# servo_shield_v1.net
KiCad netlist of a schematic drawn in EAGLE
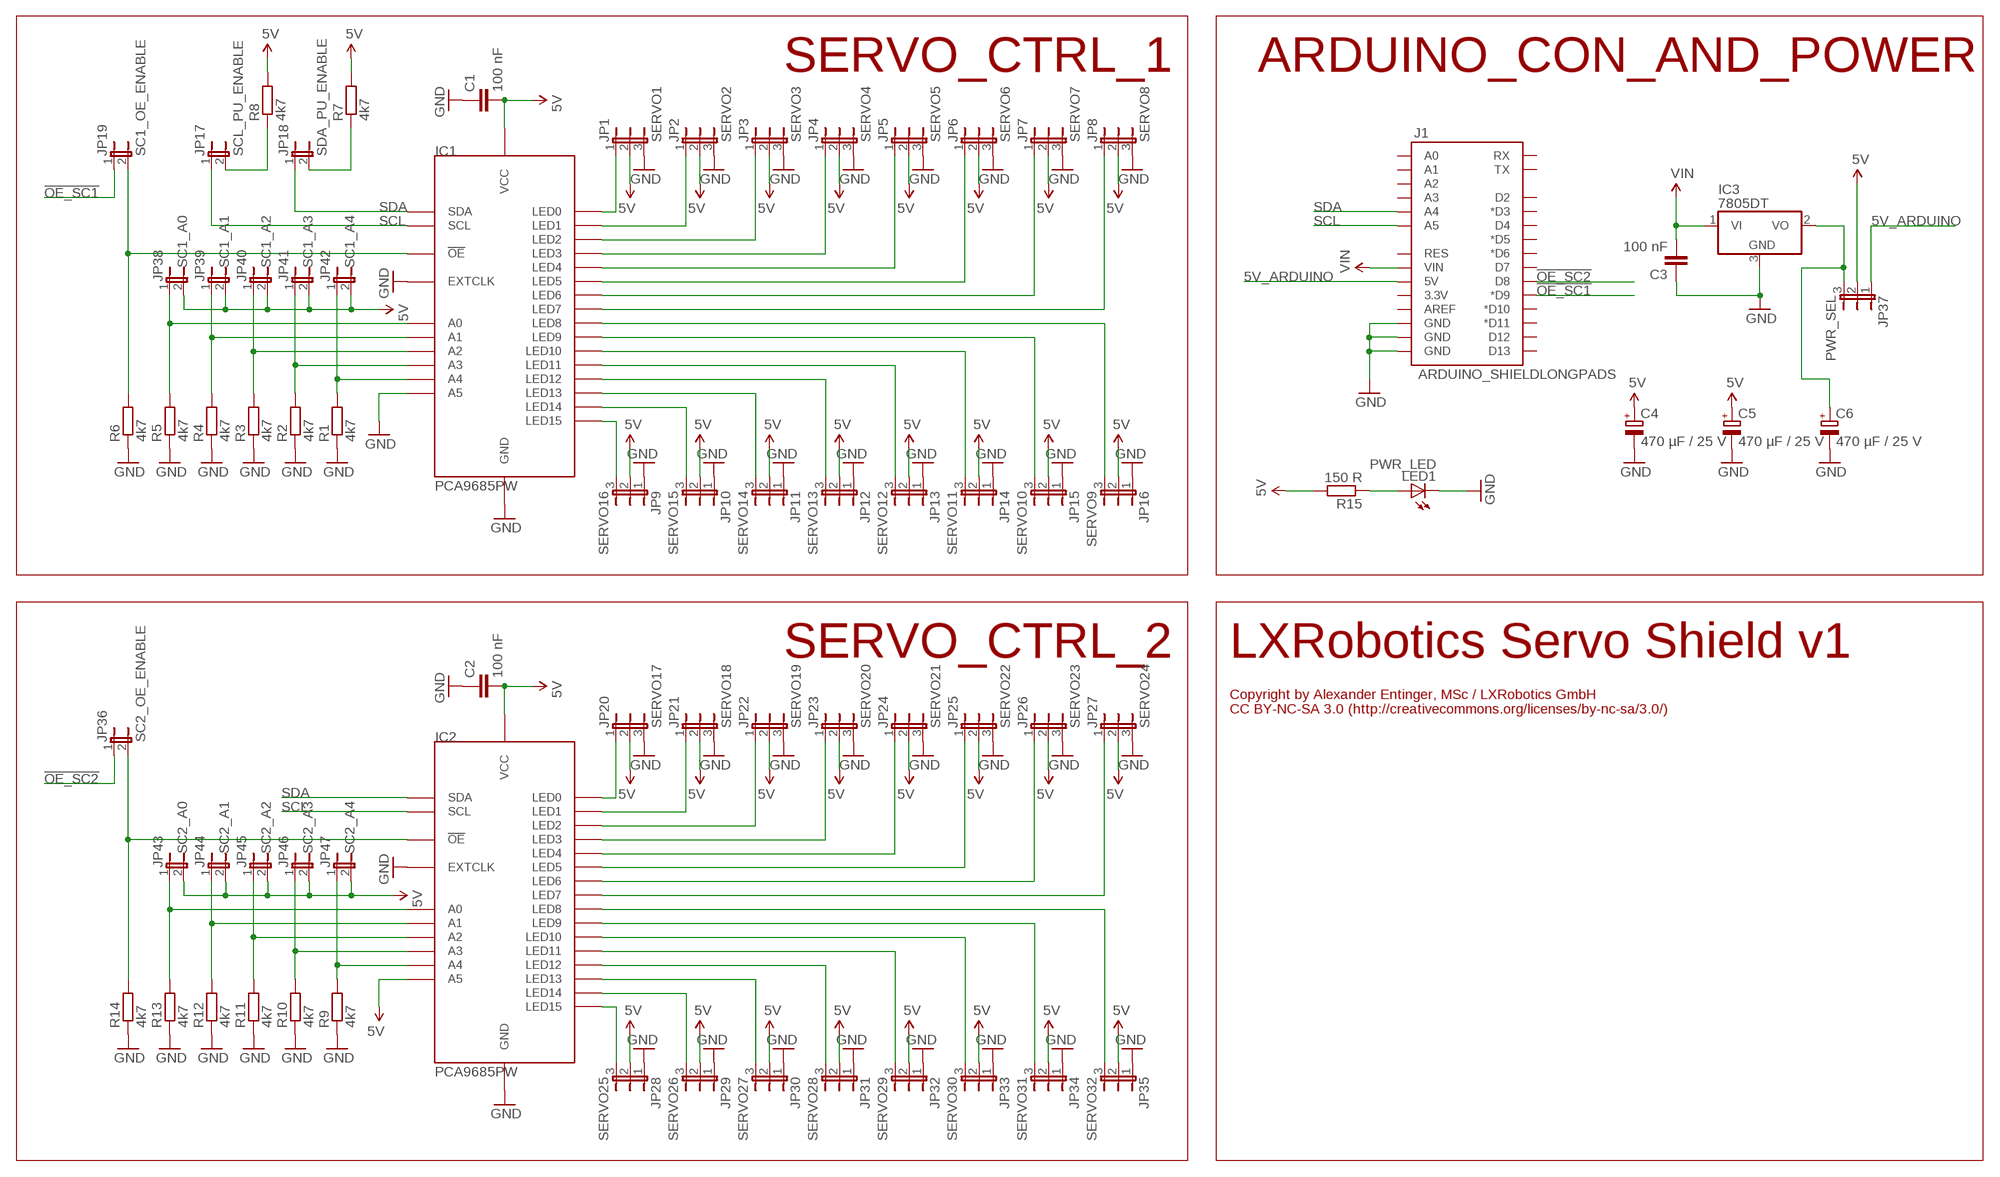
[diagram p0: schematic, sheet 1]

(export (version "E")
  (design (tool "Eeschema 10.0.6"))
  (components
    (comp (ref "C1")
      (value "100 nF")
      (footprint "eagle-import:C0805K")
      (libsource (lib "eagle-import") (part "C-EUC0805K"))
    )
    (comp (ref "C2")
      (value "100 nF")
      (footprint "eagle-import:C0805K")
      (libsource (lib "eagle-import") (part "C-EUC0805K"))
    )
    (comp (ref "C3")
      (value "100 nF")
      (footprint "eagle-import:C0805K")
      (libsource (lib "eagle-import") (part "C-EUC0805K"))
    )
    (comp (ref "C4")
      (value "470 µF / 25 V")
      (footprint "eagle-import:E5-10,5")
      (libsource (lib "eagle-import") (part "CPOL-EUE5-10.5"))
    )
    (comp (ref "C5")
      (value "470 µF / 25 V")
      (footprint "eagle-import:E5-10,5")
      (libsource (lib "eagle-import") (part "CPOL-EUE5-10.5"))
    )
    (comp (ref "C6")
      (value "470 µF / 25 V")
      (footprint "eagle-import:E5-10,5")
      (libsource (lib "eagle-import") (part "CPOL-EUE5-10.5"))
    )
    (comp (ref "IC1")
      (value "PCA9685PW")
      (footprint "eagle-import:TSSOP28")
      (libsource (lib "eagle-import") (part "PCA9685PW"))
    )
    (comp (ref "IC2")
      (value "PCA9685PW")
      (footprint "eagle-import:TSSOP28")
      (libsource (lib "eagle-import") (part "PCA9685PW"))
    )
    (comp (ref "IC3")
      (value "7805DT")
      (footprint "eagle-import:TO252")
      (libsource (lib "eagle-import") (part "78DT05"))
    )
    (comp (ref "J1")
      (value "ARDUINO_SHIELDLONGPADS")
      (footprint "eagle-import:DUEMILANOVE_SHIELD_LONGPADS")
      (libsource (lib "eagle-import") (part "ARDUINO_SHIELDLONGPADS"))
    )
    (comp (ref "JP1")
      (value "SERVO1")
      (footprint "eagle-import:JP2")
      (libsource (lib "eagle-import") (part "JP2E"))
    )
    (comp (ref "JP2")
      (value "SERVO2")
      (footprint "eagle-import:JP2")
      (libsource (lib "eagle-import") (part "JP2E"))
    )
    (comp (ref "JP3")
      (value "SERVO3")
      (footprint "eagle-import:JP2")
      (libsource (lib "eagle-import") (part "JP2E"))
    )
    (comp (ref "JP4")
      (value "SERVO4")
      (footprint "eagle-import:JP2")
      (libsource (lib "eagle-import") (part "JP2E"))
    )
    (comp (ref "JP5")
      (value "SERVO5")
      (footprint "eagle-import:JP2")
      (libsource (lib "eagle-import") (part "JP2E"))
    )
    (comp (ref "JP6")
      (value "SERVO6")
      (footprint "eagle-import:JP2")
      (libsource (lib "eagle-import") (part "JP2E"))
    )
    (comp (ref "JP7")
      (value "SERVO7")
      (footprint "eagle-import:JP2")
      (libsource (lib "eagle-import") (part "JP2E"))
    )
    (comp (ref "JP8")
      (value "SERVO8")
      (footprint "eagle-import:JP2")
      (libsource (lib "eagle-import") (part "JP2E"))
    )
    (comp (ref "JP9")
      (value "SERVO16")
      (footprint "eagle-import:JP2")
      (libsource (lib "eagle-import") (part "JP2E"))
    )
    (comp (ref "JP10")
      (value "SERVO15")
      (footprint "eagle-import:JP2")
      (libsource (lib "eagle-import") (part "JP2E"))
    )
    (comp (ref "JP11")
      (value "SERVO14")
      (footprint "eagle-import:JP2")
      (libsource (lib "eagle-import") (part "JP2E"))
    )
    (comp (ref "JP12")
      (value "SERVO13")
      (footprint "eagle-import:JP2")
      (libsource (lib "eagle-import") (part "JP2E"))
    )
    (comp (ref "JP13")
      (value "SERVO12")
      (footprint "eagle-import:JP2")
      (libsource (lib "eagle-import") (part "JP2E"))
    )
    (comp (ref "JP14")
      (value "SERVO11")
      (footprint "eagle-import:JP2")
      (libsource (lib "eagle-import") (part "JP2E"))
    )
    (comp (ref "JP15")
      (value "SERVO10")
      (footprint "eagle-import:JP2")
      (libsource (lib "eagle-import") (part "JP2E"))
    )
    (comp (ref "JP16")
      (value "SERVO9")
      (footprint "eagle-import:JP2")
      (libsource (lib "eagle-import") (part "JP2E"))
    )
    (comp (ref "JP17")
      (value "SCL_PU_ENABLE")
      (footprint "eagle-import:JP1")
      (libsource (lib "eagle-import") (part "JP1E"))
    )
    (comp (ref "JP18")
      (value "SDA_PU_ENABLE")
      (footprint "eagle-import:JP1")
      (libsource (lib "eagle-import") (part "JP1E"))
    )
    (comp (ref "JP19")
      (value "SC1_OE_ENABLE")
      (footprint "eagle-import:JP1")
      (libsource (lib "eagle-import") (part "JP1E"))
    )
    (comp (ref "JP20")
      (value "SERVO17")
      (footprint "eagle-import:JP2")
      (libsource (lib "eagle-import") (part "JP2E"))
    )
    (comp (ref "JP21")
      (value "SERVO18")
      (footprint "eagle-import:JP2")
      (libsource (lib "eagle-import") (part "JP2E"))
    )
    (comp (ref "JP22")
      (value "SERVO19")
      (footprint "eagle-import:JP2")
      (libsource (lib "eagle-import") (part "JP2E"))
    )
    (comp (ref "JP23")
      (value "SERVO20")
      (footprint "eagle-import:JP2")
      (libsource (lib "eagle-import") (part "JP2E"))
    )
    (comp (ref "JP24")
      (value "SERVO21")
      (footprint "eagle-import:JP2")
      (libsource (lib "eagle-import") (part "JP2E"))
    )
    (comp (ref "JP25")
      (value "SERVO22")
      (footprint "eagle-import:JP2")
      (libsource (lib "eagle-import") (part "JP2E"))
    )
    (comp (ref "JP26")
      (value "SERVO23")
      (footprint "eagle-import:JP2")
      (libsource (lib "eagle-import") (part "JP2E"))
    )
    (comp (ref "JP27")
      (value "SERVO24")
      (footprint "eagle-import:JP2")
      (libsource (lib "eagle-import") (part "JP2E"))
    )
    (comp (ref "JP28")
      (value "SERVO25")
      (footprint "eagle-import:JP2")
      (libsource (lib "eagle-import") (part "JP2E"))
    )
    (comp (ref "JP29")
      (value "SERVO26")
      (footprint "eagle-import:JP2")
      (libsource (lib "eagle-import") (part "JP2E"))
    )
    (comp (ref "JP30")
      (value "SERVO27")
      (footprint "eagle-import:JP2")
      (libsource (lib "eagle-import") (part "JP2E"))
    )
    (comp (ref "JP31")
      (value "SERVO28")
      (footprint "eagle-import:JP2")
      (libsource (lib "eagle-import") (part "JP2E"))
    )
    (comp (ref "JP32")
      (value "SERVO29")
      (footprint "eagle-import:JP2")
      (libsource (lib "eagle-import") (part "JP2E"))
    )
    (comp (ref "JP33")
      (value "SERVO30")
      (footprint "eagle-import:JP2")
      (libsource (lib "eagle-import") (part "JP2E"))
    )
    (comp (ref "JP34")
      (value "SERVO31")
      (footprint "eagle-import:JP2")
      (libsource (lib "eagle-import") (part "JP2E"))
    )
    (comp (ref "JP35")
      (value "SERVO32")
      (footprint "eagle-import:JP2")
      (libsource (lib "eagle-import") (part "JP2E"))
    )
    (comp (ref "JP36")
      (value "SC2_OE_ENABLE")
      (footprint "eagle-import:JP1")
      (libsource (lib "eagle-import") (part "JP1E"))
    )
    (comp (ref "JP37")
      (value "PWR_SEL")
      (footprint "eagle-import:JP2")
      (libsource (lib "eagle-import") (part "JP2E"))
    )
    (comp (ref "JP38")
      (value "SC1_A0")
      (footprint "eagle-import:JP1")
      (libsource (lib "eagle-import") (part "JP1E"))
    )
    (comp (ref "JP39")
      (value "SC1_A1")
      (footprint "eagle-import:JP1")
      (libsource (lib "eagle-import") (part "JP1E"))
    )
    (comp (ref "JP40")
      (value "SC1_A2")
      (footprint "eagle-import:JP1")
      (libsource (lib "eagle-import") (part "JP1E"))
    )
    (comp (ref "JP41")
      (value "SC1_A3")
      (footprint "eagle-import:JP1")
      (libsource (lib "eagle-import") (part "JP1E"))
    )
    (comp (ref "JP42")
      (value "SC1_A4")
      (footprint "eagle-import:JP1")
      (libsource (lib "eagle-import") (part "JP1E"))
    )
    (comp (ref "JP43")
      (value "SC2_A0")
      (footprint "eagle-import:JP1")
      (libsource (lib "eagle-import") (part "JP1E"))
    )
    (comp (ref "JP44")
      (value "SC2_A1")
      (footprint "eagle-import:JP1")
      (libsource (lib "eagle-import") (part "JP1E"))
    )
    (comp (ref "JP45")
      (value "SC2_A2")
      (footprint "eagle-import:JP1")
      (libsource (lib "eagle-import") (part "JP1E"))
    )
    (comp (ref "JP46")
      (value "SC2_A3")
      (footprint "eagle-import:JP1")
      (libsource (lib "eagle-import") (part "JP1E"))
    )
    (comp (ref "JP47")
      (value "SC2_A4")
      (footprint "eagle-import:JP1")
      (libsource (lib "eagle-import") (part "JP1E"))
    )
    (comp (ref "LED1")
      (value "PWR_LED")
      (footprint "eagle-import:CHIPLED_0805")
      (libsource (lib "eagle-import") (part "LEDCHIPLED_0805"))
    )
    (comp (ref "R1")
      (value "4k7")
      (footprint "eagle-import:R0805W")
      (libsource (lib "eagle-import") (part "R-EU_R0805W"))
    )
    (comp (ref "R2")
      (value "4k7")
      (footprint "eagle-import:R0805W")
      (libsource (lib "eagle-import") (part "R-EU_R0805W"))
    )
    (comp (ref "R3")
      (value "4k7")
      (footprint "eagle-import:R0805W")
      (libsource (lib "eagle-import") (part "R-EU_R0805W"))
    )
    (comp (ref "R4")
      (value "4k7")
      (footprint "eagle-import:R0805W")
      (libsource (lib "eagle-import") (part "R-EU_R0805W"))
    )
    (comp (ref "R5")
      (value "4k7")
      (footprint "eagle-import:R0805W")
      (libsource (lib "eagle-import") (part "R-EU_R0805W"))
    )
    (comp (ref "R6")
      (value "4k7")
      (footprint "eagle-import:R0805W")
      (libsource (lib "eagle-import") (part "R-EU_R0805W"))
    )
    (comp (ref "R7")
      (value "4k7")
      (footprint "eagle-import:R0805W")
      (libsource (lib "eagle-import") (part "R-EU_R0805W"))
    )
    (comp (ref "R8")
      (value "4k7")
      (footprint "eagle-import:R0805W")
      (libsource (lib "eagle-import") (part "R-EU_R0805W"))
    )
    (comp (ref "R9")
      (value "4k7")
      (footprint "eagle-import:R0805W")
      (libsource (lib "eagle-import") (part "R-EU_R0805W"))
    )
    (comp (ref "R10")
      (value "4k7")
      (footprint "eagle-import:R0805W")
      (libsource (lib "eagle-import") (part "R-EU_R0805W"))
    )
    (comp (ref "R11")
      (value "4k7")
      (footprint "eagle-import:R0805W")
      (libsource (lib "eagle-import") (part "R-EU_R0805W"))
    )
    (comp (ref "R12")
      (value "4k7")
      (footprint "eagle-import:R0805W")
      (libsource (lib "eagle-import") (part "R-EU_R0805W"))
    )
    (comp (ref "R13")
      (value "4k7")
      (footprint "eagle-import:R0805W")
      (libsource (lib "eagle-import") (part "R-EU_R0805W"))
    )
    (comp (ref "R14")
      (value "4k7")
      (footprint "eagle-import:R0805W")
      (libsource (lib "eagle-import") (part "R-EU_R0805W"))
    )
    (comp (ref "R15")
      (value "150 R")
      (footprint "eagle-import:R0805W")
      (libsource (lib "eagle-import") (part "R-EU_R0805W"))
    )
  )
  (nets
    (net (code "1") (name "/5V_ARDUINO") (class "Default")
      (node (ref "J1") (pin "5V") (pinfunction "5V_5V") (pintype "bidirectional"))
      (node (ref "JP37") (pin "1") (pinfunction "1_1") (pintype "passive"))
    )
    (net (code "2") (name "/SCL") (class "Default")
      (node (ref "IC1") (pin "26") (pinfunction "SCL_26") (pintype "bidirectional"))
      (node (ref "IC2") (pin "26") (pinfunction "SCL_26") (pintype "bidirectional"))
      (node (ref "J1") (pin "A5") (pinfunction "A5_A5") (pintype "bidirectional"))
      (node (ref "JP17") (pin "1") (pinfunction "1_1") (pintype "passive"))
    )
    (net (code "3") (name "/SDA") (class "Default")
      (node (ref "IC1") (pin "27") (pinfunction "SDA_27") (pintype "bidirectional"))
      (node (ref "IC2") (pin "27") (pinfunction "SDA_27") (pintype "bidirectional"))
      (node (ref "J1") (pin "A4") (pinfunction "A4_A4") (pintype "bidirectional"))
      (node (ref "JP18") (pin "1") (pinfunction "1_1") (pintype "passive"))
    )
    (net (code "4") (name "/~{OE_SC1}") (class "Default")
      (node (ref "J1") (pin "D9") (pinfunction "*D9_D9") (pintype "bidirectional"))
      (node (ref "JP19") (pin "1") (pinfunction "1_1") (pintype "passive"))
    )
    (net (code "5") (name "/~{OE_SC2}") (class "Default")
      (node (ref "J1") (pin "D8") (pinfunction "D8_D8") (pintype "bidirectional"))
      (node (ref "JP36") (pin "1") (pinfunction "1_1") (pintype "passive"))
    )
    (net (code "6") (name "5V") (class "Default")
      (node (ref "C1") (pin "2") (pinfunction "2_2") (pintype "passive"))
      (node (ref "C2") (pin "2") (pinfunction "2_2") (pintype "passive"))
      (node (ref "C4") (pin "+") (pinfunction "+_+") (pintype "passive"))
      (node (ref "C5") (pin "+") (pinfunction "+_+") (pintype "passive"))
      (node (ref "IC1") (pin "28") (pinfunction "VCC_28") (pintype "bidirectional"))
      (node (ref "IC2") (pin "24") (pinfunction "A5_24") (pintype "bidirectional"))
      (node (ref "IC2") (pin "28") (pinfunction "VCC_28") (pintype "bidirectional"))
      (node (ref "JP1") (pin "2") (pinfunction "2_2") (pintype "passive"))
      (node (ref "JP10") (pin "2") (pinfunction "2_2") (pintype "passive"))
      (node (ref "JP11") (pin "2") (pinfunction "2_2") (pintype "passive"))
      (node (ref "JP12") (pin "2") (pinfunction "2_2") (pintype "passive"))
      (node (ref "JP13") (pin "2") (pinfunction "2_2") (pintype "passive"))
      (node (ref "JP14") (pin "2") (pinfunction "2_2") (pintype "passive"))
      (node (ref "JP15") (pin "2") (pinfunction "2_2") (pintype "passive"))
      (node (ref "JP16") (pin "2") (pinfunction "2_2") (pintype "passive"))
      (node (ref "JP2") (pin "2") (pinfunction "2_2") (pintype "passive"))
      (node (ref "JP20") (pin "2") (pinfunction "2_2") (pintype "passive"))
      (node (ref "JP21") (pin "2") (pinfunction "2_2") (pintype "passive"))
      (node (ref "JP22") (pin "2") (pinfunction "2_2") (pintype "passive"))
      (node (ref "JP23") (pin "2") (pinfunction "2_2") (pintype "passive"))
      (node (ref "JP24") (pin "2") (pinfunction "2_2") (pintype "passive"))
      (node (ref "JP25") (pin "2") (pinfunction "2_2") (pintype "passive"))
      (node (ref "JP26") (pin "2") (pinfunction "2_2") (pintype "passive"))
      (node (ref "JP27") (pin "2") (pinfunction "2_2") (pintype "passive"))
      (node (ref "JP28") (pin "2") (pinfunction "2_2") (pintype "passive"))
      (node (ref "JP29") (pin "2") (pinfunction "2_2") (pintype "passive"))
      (node (ref "JP3") (pin "2") (pinfunction "2_2") (pintype "passive"))
      (node (ref "JP30") (pin "2") (pinfunction "2_2") (pintype "passive"))
      (node (ref "JP31") (pin "2") (pinfunction "2_2") (pintype "passive"))
      (node (ref "JP32") (pin "2") (pinfunction "2_2") (pintype "passive"))
      (node (ref "JP33") (pin "2") (pinfunction "2_2") (pintype "passive"))
      (node (ref "JP34") (pin "2") (pinfunction "2_2") (pintype "passive"))
      (node (ref "JP35") (pin "2") (pinfunction "2_2") (pintype "passive"))
      (node (ref "JP37") (pin "2") (pinfunction "2_2") (pintype "passive"))
      (node (ref "JP38") (pin "2") (pinfunction "2_2") (pintype "passive"))
      (node (ref "JP39") (pin "2") (pinfunction "2_2") (pintype "passive"))
      (node (ref "JP4") (pin "2") (pinfunction "2_2") (pintype "passive"))
      (node (ref "JP40") (pin "2") (pinfunction "2_2") (pintype "passive"))
      (node (ref "JP41") (pin "2") (pinfunction "2_2") (pintype "passive"))
      (node (ref "JP42") (pin "2") (pinfunction "2_2") (pintype "passive"))
      (node (ref "JP43") (pin "2") (pinfunction "2_2") (pintype "passive"))
      (node (ref "JP44") (pin "2") (pinfunction "2_2") (pintype "passive"))
      (node (ref "JP45") (pin "2") (pinfunction "2_2") (pintype "passive"))
      (node (ref "JP46") (pin "2") (pinfunction "2_2") (pintype "passive"))
      (node (ref "JP47") (pin "2") (pinfunction "2_2") (pintype "passive"))
      (node (ref "JP5") (pin "2") (pinfunction "2_2") (pintype "passive"))
      (node (ref "JP6") (pin "2") (pinfunction "2_2") (pintype "passive"))
      (node (ref "JP7") (pin "2") (pinfunction "2_2") (pintype "passive"))
      (node (ref "JP8") (pin "2") (pinfunction "2_2") (pintype "passive"))
      (node (ref "JP9") (pin "2") (pinfunction "2_2") (pintype "passive"))
      (node (ref "R15") (pin "2") (pinfunction "2_2") (pintype "passive"))
      (node (ref "R7") (pin "2") (pinfunction "2_2") (pintype "passive"))
      (node (ref "R8") (pin "2") (pinfunction "2_2") (pintype "passive"))
    )
    (net (code "7") (name "GND") (class "Default")
      (node (ref "C1") (pin "1") (pinfunction "1_1") (pintype "passive"))
      (node (ref "C2") (pin "1") (pinfunction "1_1") (pintype "passive"))
      (node (ref "C3") (pin "1") (pinfunction "1_1") (pintype "passive"))
      (node (ref "C4") (pin "-") (pinfunction "-_-") (pintype "passive"))
      (node (ref "C5") (pin "-") (pinfunction "-_-") (pintype "passive"))
      (node (ref "C6") (pin "-") (pinfunction "-_-") (pintype "passive"))
      (node (ref "IC1") (pin "14") (pinfunction "GND_14") (pintype "bidirectional"))
      (node (ref "IC1") (pin "24") (pinfunction "A5_24") (pintype "bidirectional"))
      (node (ref "IC1") (pin "25") (pinfunction "EXTCLK_25") (pintype "bidirectional"))
      (node (ref "IC2") (pin "14") (pinfunction "GND_14") (pintype "bidirectional"))
      (node (ref "IC2") (pin "25") (pinfunction "EXTCLK_25") (pintype "bidirectional"))
      (node (ref "IC3") (pin "3") (pinfunction "GND_3") (pintype "passive"))
      (node (ref "J1") (pin "GND@0") (pinfunction "GND_GND@0") (pintype "bidirectional"))
      (node (ref "J1") (pin "GND@1") (pinfunction "GND_GND@1") (pintype "bidirectional"))
      (node (ref "J1") (pin "GND@2") (pinfunction "GND_GND@2") (pintype "bidirectional"))
      (node (ref "JP1") (pin "3") (pinfunction "3_3") (pintype "passive"))
      (node (ref "JP10") (pin "1") (pinfunction "1_1") (pintype "passive"))
      (node (ref "JP11") (pin "1") (pinfunction "1_1") (pintype "passive"))
      (node (ref "JP12") (pin "1") (pinfunction "1_1") (pintype "passive"))
      (node (ref "JP13") (pin "1") (pinfunction "1_1") (pintype "passive"))
      (node (ref "JP14") (pin "1") (pinfunction "1_1") (pintype "passive"))
      (node (ref "JP15") (pin "1") (pinfunction "1_1") (pintype "passive"))
      (node (ref "JP16") (pin "1") (pinfunction "1_1") (pintype "passive"))
      (node (ref "JP2") (pin "3") (pinfunction "3_3") (pintype "passive"))
      (node (ref "JP20") (pin "3") (pinfunction "3_3") (pintype "passive"))
      (node (ref "JP21") (pin "3") (pinfunction "3_3") (pintype "passive"))
      (node (ref "JP22") (pin "3") (pinfunction "3_3") (pintype "passive"))
      (node (ref "JP23") (pin "3") (pinfunction "3_3") (pintype "passive"))
      (node (ref "JP24") (pin "3") (pinfunction "3_3") (pintype "passive"))
      (node (ref "JP25") (pin "3") (pinfunction "3_3") (pintype "passive"))
      (node (ref "JP26") (pin "3") (pinfunction "3_3") (pintype "passive"))
      (node (ref "JP27") (pin "3") (pinfunction "3_3") (pintype "passive"))
      (node (ref "JP28") (pin "1") (pinfunction "1_1") (pintype "passive"))
      (node (ref "JP29") (pin "1") (pinfunction "1_1") (pintype "passive"))
      (node (ref "JP3") (pin "3") (pinfunction "3_3") (pintype "passive"))
      (node (ref "JP30") (pin "1") (pinfunction "1_1") (pintype "passive"))
      (node (ref "JP31") (pin "1") (pinfunction "1_1") (pintype "passive"))
      (node (ref "JP32") (pin "1") (pinfunction "1_1") (pintype "passive"))
      (node (ref "JP33") (pin "1") (pinfunction "1_1") (pintype "passive"))
      (node (ref "JP34") (pin "1") (pinfunction "1_1") (pintype "passive"))
      (node (ref "JP35") (pin "1") (pinfunction "1_1") (pintype "passive"))
      (node (ref "JP4") (pin "3") (pinfunction "3_3") (pintype "passive"))
      (node (ref "JP5") (pin "3") (pinfunction "3_3") (pintype "passive"))
      (node (ref "JP6") (pin "3") (pinfunction "3_3") (pintype "passive"))
      (node (ref "JP7") (pin "3") (pinfunction "3_3") (pintype "passive"))
      (node (ref "JP8") (pin "3") (pinfunction "3_3") (pintype "passive"))
      (node (ref "JP9") (pin "1") (pinfunction "1_1") (pintype "passive"))
      (node (ref "LED1") (pin "C") (pinfunction "C_C") (pintype "passive"))
      (node (ref "R1") (pin "1") (pinfunction "1_1") (pintype "passive"))
      (node (ref "R10") (pin "1") (pinfunction "1_1") (pintype "passive"))
      (node (ref "R11") (pin "1") (pinfunction "1_1") (pintype "passive"))
      (node (ref "R12") (pin "1") (pinfunction "1_1") (pintype "passive"))
      (node (ref "R13") (pin "1") (pinfunction "1_1") (pintype "passive"))
      (node (ref "R14") (pin "1") (pinfunction "1_1") (pintype "passive"))
      (node (ref "R2") (pin "1") (pinfunction "1_1") (pintype "passive"))
      (node (ref "R3") (pin "1") (pinfunction "1_1") (pintype "passive"))
      (node (ref "R4") (pin "1") (pinfunction "1_1") (pintype "passive"))
      (node (ref "R5") (pin "1") (pinfunction "1_1") (pintype "passive"))
      (node (ref "R6") (pin "1") (pinfunction "1_1") (pintype "passive"))
      (node (ref "R9") (pin "1") (pinfunction "1_1") (pintype "passive"))
    )
    (net (code "8") (name "Net-(IC1-A0)") (class "Default")
      (node (ref "IC1") (pin "1") (pinfunction "A0_1") (pintype "bidirectional"))
      (node (ref "JP38") (pin "1") (pinfunction "1_1") (pintype "passive"))
      (node (ref "R5") (pin "2") (pinfunction "2_2") (pintype "passive"))
    )
    (net (code "9") (name "Net-(IC1-A1)") (class "Default")
      (node (ref "IC1") (pin "2") (pinfunction "A1_2") (pintype "bidirectional"))
      (node (ref "JP39") (pin "1") (pinfunction "1_1") (pintype "passive"))
      (node (ref "R4") (pin "2") (pinfunction "2_2") (pintype "passive"))
    )
    (net (code "10") (name "Net-(IC1-A2)") (class "Default")
      (node (ref "IC1") (pin "3") (pinfunction "A2_3") (pintype "bidirectional"))
      (node (ref "JP40") (pin "1") (pinfunction "1_1") (pintype "passive"))
      (node (ref "R3") (pin "2") (pinfunction "2_2") (pintype "passive"))
    )
    (net (code "11") (name "Net-(IC1-A3)") (class "Default")
      (node (ref "IC1") (pin "4") (pinfunction "A3_4") (pintype "bidirectional"))
      (node (ref "JP41") (pin "1") (pinfunction "1_1") (pintype "passive"))
      (node (ref "R2") (pin "2") (pinfunction "2_2") (pintype "passive"))
    )
    (net (code "12") (name "Net-(IC1-A4)") (class "Default")
      (node (ref "IC1") (pin "5") (pinfunction "A4_5") (pintype "bidirectional"))
      (node (ref "JP42") (pin "1") (pinfunction "1_1") (pintype "passive"))
      (node (ref "R1") (pin "2") (pinfunction "2_2") (pintype "passive"))
    )
    (net (code "13") (name "Net-(IC1-LED0)") (class "Default")
      (node (ref "IC1") (pin "6") (pinfunction "LED0_6") (pintype "bidirectional"))
      (node (ref "JP1") (pin "1") (pinfunction "1_1") (pintype "passive"))
    )
    (net (code "14") (name "Net-(IC1-LED1)") (class "Default")
      (node (ref "IC1") (pin "7") (pinfunction "LED1_7") (pintype "bidirectional"))
      (node (ref "JP2") (pin "1") (pinfunction "1_1") (pintype "passive"))
    )
    (net (code "15") (name "Net-(IC1-LED2)") (class "Default")
      (node (ref "IC1") (pin "8") (pinfunction "LED2_8") (pintype "bidirectional"))
      (node (ref "JP3") (pin "1") (pinfunction "1_1") (pintype "passive"))
    )
    (net (code "16") (name "Net-(IC1-LED3)") (class "Default")
      (node (ref "IC1") (pin "9") (pinfunction "LED3_9") (pintype "bidirectional"))
      (node (ref "JP4") (pin "1") (pinfunction "1_1") (pintype "passive"))
    )
    (net (code "17") (name "Net-(IC1-LED4)") (class "Default")
      (node (ref "IC1") (pin "10") (pinfunction "LED4_10") (pintype "bidirectional"))
      (node (ref "JP5") (pin "1") (pinfunction "1_1") (pintype "passive"))
    )
    (net (code "18") (name "Net-(IC1-LED5)") (class "Default")
      (node (ref "IC1") (pin "11") (pinfunction "LED5_11") (pintype "bidirectional"))
      (node (ref "JP6") (pin "1") (pinfunction "1_1") (pintype "passive"))
    )
    (net (code "19") (name "Net-(IC1-LED6)") (class "Default")
      (node (ref "IC1") (pin "12") (pinfunction "LED6_12") (pintype "bidirectional"))
      (node (ref "JP7") (pin "1") (pinfunction "1_1") (pintype "passive"))
    )
    (net (code "20") (name "Net-(IC1-LED7)") (class "Default")
      (node (ref "IC1") (pin "13") (pinfunction "LED7_13") (pintype "bidirectional"))
      (node (ref "JP8") (pin "1") (pinfunction "1_1") (pintype "passive"))
    )
    (net (code "21") (name "Net-(IC1-LED8)") (class "Default")
      (node (ref "IC1") (pin "15") (pinfunction "LED8_15") (pintype "bidirectional"))
      (node (ref "JP16") (pin "3") (pinfunction "3_3") (pintype "passive"))
    )
    (net (code "22") (name "Net-(IC1-LED9)") (class "Default")
      (node (ref "IC1") (pin "16") (pinfunction "LED9_16") (pintype "bidirectional"))
      (node (ref "JP15") (pin "3") (pinfunction "3_3") (pintype "passive"))
    )
    (net (code "23") (name "Net-(IC1-LED10)") (class "Default")
      (node (ref "IC1") (pin "17") (pinfunction "LED10_17") (pintype "bidirectional"))
      (node (ref "JP14") (pin "3") (pinfunction "3_3") (pintype "passive"))
    )
    (net (code "24") (name "Net-(IC1-LED11)") (class "Default")
      (node (ref "IC1") (pin "18") (pinfunction "LED11_18") (pintype "bidirectional"))
      (node (ref "JP13") (pin "3") (pinfunction "3_3") (pintype "passive"))
    )
    (net (code "25") (name "Net-(IC1-LED12)") (class "Default")
      (node (ref "IC1") (pin "19") (pinfunction "LED12_19") (pintype "bidirectional"))
      (node (ref "JP12") (pin "3") (pinfunction "3_3") (pintype "passive"))
    )
    (net (code "26") (name "Net-(IC1-LED13)") (class "Default")
      (node (ref "IC1") (pin "20") (pinfunction "LED13_20") (pintype "bidirectional"))
      (node (ref "JP11") (pin "3") (pinfunction "3_3") (pintype "passive"))
    )
    (net (code "27") (name "Net-(IC1-LED14)") (class "Default")
      (node (ref "IC1") (pin "21") (pinfunction "LED14_21") (pintype "bidirectional"))
      (node (ref "JP10") (pin "3") (pinfunction "3_3") (pintype "passive"))
    )
    (net (code "28") (name "Net-(IC1-LED15)") (class "Default")
      (node (ref "IC1") (pin "22") (pinfunction "LED15_22") (pintype "bidirectional"))
      (node (ref "JP9") (pin "3") (pinfunction "3_3") (pintype "passive"))
    )
    (net (code "29") (name "Net-(IC1-~{OE})") (class "Default")
      (node (ref "IC1") (pin "23") (pinfunction "~{OE}_23") (pintype "bidirectional"))
      (node (ref "JP19") (pin "2") (pinfunction "2_2") (pintype "passive"))
      (node (ref "R6") (pin "2") (pinfunction "2_2") (pintype "passive"))
    )
    (net (code "30") (name "Net-(IC2-A0)") (class "Default")
      (node (ref "IC2") (pin "1") (pinfunction "A0_1") (pintype "bidirectional"))
      (node (ref "JP43") (pin "1") (pinfunction "1_1") (pintype "passive"))
      (node (ref "R13") (pin "2") (pinfunction "2_2") (pintype "passive"))
    )
    (net (code "31") (name "Net-(IC2-A1)") (class "Default")
      (node (ref "IC2") (pin "2") (pinfunction "A1_2") (pintype "bidirectional"))
      (node (ref "JP44") (pin "1") (pinfunction "1_1") (pintype "passive"))
      (node (ref "R12") (pin "2") (pinfunction "2_2") (pintype "passive"))
    )
    (net (code "32") (name "Net-(IC2-A2)") (class "Default")
      (node (ref "IC2") (pin "3") (pinfunction "A2_3") (pintype "bidirectional"))
      (node (ref "JP45") (pin "1") (pinfunction "1_1") (pintype "passive"))
      (node (ref "R11") (pin "2") (pinfunction "2_2") (pintype "passive"))
    )
    (net (code "33") (name "Net-(IC2-A3)") (class "Default")
      (node (ref "IC2") (pin "4") (pinfunction "A3_4") (pintype "bidirectional"))
      (node (ref "JP46") (pin "1") (pinfunction "1_1") (pintype "passive"))
      (node (ref "R10") (pin "2") (pinfunction "2_2") (pintype "passive"))
    )
    (net (code "34") (name "Net-(IC2-A4)") (class "Default")
      (node (ref "IC2") (pin "5") (pinfunction "A4_5") (pintype "bidirectional"))
      (node (ref "JP47") (pin "1") (pinfunction "1_1") (pintype "passive"))
      (node (ref "R9") (pin "2") (pinfunction "2_2") (pintype "passive"))
    )
    (net (code "35") (name "Net-(IC2-LED0)") (class "Default")
      (node (ref "IC2") (pin "6") (pinfunction "LED0_6") (pintype "bidirectional"))
      (node (ref "JP20") (pin "1") (pinfunction "1_1") (pintype "passive"))
    )
    (net (code "36") (name "Net-(IC2-LED1)") (class "Default")
      (node (ref "IC2") (pin "7") (pinfunction "LED1_7") (pintype "bidirectional"))
      (node (ref "JP21") (pin "1") (pinfunction "1_1") (pintype "passive"))
    )
    (net (code "37") (name "Net-(IC2-LED2)") (class "Default")
      (node (ref "IC2") (pin "8") (pinfunction "LED2_8") (pintype "bidirectional"))
      (node (ref "JP22") (pin "1") (pinfunction "1_1") (pintype "passive"))
    )
    (net (code "38") (name "Net-(IC2-LED3)") (class "Default")
      (node (ref "IC2") (pin "9") (pinfunction "LED3_9") (pintype "bidirectional"))
      (node (ref "JP23") (pin "1") (pinfunction "1_1") (pintype "passive"))
    )
    (net (code "39") (name "Net-(IC2-LED4)") (class "Default")
      (node (ref "IC2") (pin "10") (pinfunction "LED4_10") (pintype "bidirectional"))
      (node (ref "JP24") (pin "1") (pinfunction "1_1") (pintype "passive"))
    )
    (net (code "40") (name "Net-(IC2-LED5)") (class "Default")
      (node (ref "IC2") (pin "11") (pinfunction "LED5_11") (pintype "bidirectional"))
      (node (ref "JP25") (pin "1") (pinfunction "1_1") (pintype "passive"))
    )
    (net (code "41") (name "Net-(IC2-LED6)") (class "Default")
      (node (ref "IC2") (pin "12") (pinfunction "LED6_12") (pintype "bidirectional"))
      (node (ref "JP26") (pin "1") (pinfunction "1_1") (pintype "passive"))
    )
    (net (code "42") (name "Net-(IC2-LED7)") (class "Default")
      (node (ref "IC2") (pin "13") (pinfunction "LED7_13") (pintype "bidirectional"))
      (node (ref "JP27") (pin "1") (pinfunction "1_1") (pintype "passive"))
    )
    (net (code "43") (name "Net-(IC2-LED8)") (class "Default")
      (node (ref "IC2") (pin "15") (pinfunction "LED8_15") (pintype "bidirectional"))
      (node (ref "JP35") (pin "3") (pinfunction "3_3") (pintype "passive"))
    )
    (net (code "44") (name "Net-(IC2-LED9)") (class "Default")
      (node (ref "IC2") (pin "16") (pinfunction "LED9_16") (pintype "bidirectional"))
      (node (ref "JP34") (pin "3") (pinfunction "3_3") (pintype "passive"))
    )
    (net (code "45") (name "Net-(IC2-LED10)") (class "Default")
      (node (ref "IC2") (pin "17") (pinfunction "LED10_17") (pintype "bidirectional"))
      (node (ref "JP33") (pin "3") (pinfunction "3_3") (pintype "passive"))
    )
    (net (code "46") (name "Net-(IC2-LED11)") (class "Default")
      (node (ref "IC2") (pin "18") (pinfunction "LED11_18") (pintype "bidirectional"))
      (node (ref "JP32") (pin "3") (pinfunction "3_3") (pintype "passive"))
    )
    (net (code "47") (name "Net-(IC2-LED12)") (class "Default")
      (node (ref "IC2") (pin "19") (pinfunction "LED12_19") (pintype "bidirectional"))
      (node (ref "JP31") (pin "3") (pinfunction "3_3") (pintype "passive"))
    )
    (net (code "48") (name "Net-(IC2-LED13)") (class "Default")
      (node (ref "IC2") (pin "20") (pinfunction "LED13_20") (pintype "bidirectional"))
      (node (ref "JP30") (pin "3") (pinfunction "3_3") (pintype "passive"))
    )
    (net (code "49") (name "Net-(IC2-LED14)") (class "Default")
      (node (ref "IC2") (pin "21") (pinfunction "LED14_21") (pintype "bidirectional"))
      (node (ref "JP29") (pin "3") (pinfunction "3_3") (pintype "passive"))
    )
    (net (code "50") (name "Net-(IC2-LED15)") (class "Default")
      (node (ref "IC2") (pin "22") (pinfunction "LED15_22") (pintype "bidirectional"))
      (node (ref "JP28") (pin "3") (pinfunction "3_3") (pintype "passive"))
    )
    (net (code "51") (name "Net-(IC2-~{OE})") (class "Default")
      (node (ref "IC2") (pin "23") (pinfunction "~{OE}_23") (pintype "bidirectional"))
      (node (ref "JP36") (pin "2") (pinfunction "2_2") (pintype "passive"))
      (node (ref "R14") (pin "2") (pinfunction "2_2") (pintype "passive"))
    )
    (net (code "52") (name "Net-(IC3-VO)") (class "Default")
      (node (ref "C6") (pin "+") (pinfunction "+_+") (pintype "passive"))
      (node (ref "IC3") (pin "2") (pinfunction "VO_2") (pintype "passive"))
      (node (ref "JP37") (pin "3") (pinfunction "3_3") (pintype "passive"))
    )
    (net (code "53") (name "Net-(JP17-Pad2)") (class "Default")
      (node (ref "JP17") (pin "2") (pinfunction "2_2") (pintype "passive"))
      (node (ref "R8") (pin "1") (pinfunction "1_1") (pintype "passive"))
    )
    (net (code "54") (name "Net-(JP18-Pad2)") (class "Default")
      (node (ref "JP18") (pin "2") (pinfunction "2_2") (pintype "passive"))
      (node (ref "R7") (pin "1") (pinfunction "1_1") (pintype "passive"))
    )
    (net (code "55") (name "Net-(LED1-PadA)") (class "Default")
      (node (ref "LED1") (pin "A") (pinfunction "A_A") (pintype "passive"))
      (node (ref "R15") (pin "1") (pinfunction "1_1") (pintype "passive"))
    )
    (net (code "56") (name "VIN") (class "Default")
      (node (ref "C3") (pin "2") (pinfunction "2_2") (pintype "passive"))
      (node (ref "IC3") (pin "1") (pinfunction "VI_1") (pintype "input"))
      (node (ref "J1") (pin "VIN") (pinfunction "VIN_VIN") (pintype "bidirectional"))
    )
    (net (code "57") (name "unconnected-(J1-*D3-PadD3)") (class "Default")
      (node (ref "J1") (pin "D3") (pinfunction "*D3_D3") (pintype "bidirectional"))
    )
    (net (code "58") (name "unconnected-(J1-*D5-PadD5)") (class "Default")
      (node (ref "J1") (pin "D5") (pinfunction "*D5_D5") (pintype "bidirectional"))
    )
    (net (code "59") (name "unconnected-(J1-*D6-PadD6)") (class "Default")
      (node (ref "J1") (pin "D6") (pinfunction "*D6_D6") (pintype "bidirectional"))
    )
    (net (code "60") (name "unconnected-(J1-*D10-PadD10)") (class "Default")
      (node (ref "J1") (pin "D10") (pinfunction "*D10_D10") (pintype "bidirectional"))
    )
    (net (code "61") (name "unconnected-(J1-*D11-PadD11)") (class "Default")
      (node (ref "J1") (pin "D11") (pinfunction "*D11_D11") (pintype "bidirectional"))
    )
    (net (code "62") (name "unconnected-(J1-Pad3.3V)") (class "Default")
      (node (ref "J1") (pin "3.3V") (pinfunction "3.3V_3.3V") (pintype "bidirectional"))
    )
    (net (code "63") (name "unconnected-(J1-PadA0)") (class "Default")
      (node (ref "J1") (pin "A0") (pinfunction "A0_A0") (pintype "bidirectional"))
    )
    (net (code "64") (name "unconnected-(J1-PadA1)") (class "Default")
      (node (ref "J1") (pin "A1") (pinfunction "A1_A1") (pintype "bidirectional"))
    )
    (net (code "65") (name "unconnected-(J1-PadA2)") (class "Default")
      (node (ref "J1") (pin "A2") (pinfunction "A2_A2") (pintype "bidirectional"))
    )
    (net (code "66") (name "unconnected-(J1-PadA3)") (class "Default")
      (node (ref "J1") (pin "A3") (pinfunction "A3_A3") (pintype "bidirectional"))
    )
    (net (code "67") (name "unconnected-(J1-PadAREF)") (class "Default")
      (node (ref "J1") (pin "AREF") (pinfunction "AREF_AREF") (pintype "bidirectional"))
    )
    (net (code "68") (name "unconnected-(J1-PadD2)") (class "Default")
      (node (ref "J1") (pin "D2") (pinfunction "D2_D2") (pintype "bidirectional"))
    )
    (net (code "69") (name "unconnected-(J1-PadD4)") (class "Default")
      (node (ref "J1") (pin "D4") (pinfunction "D4_D4") (pintype "bidirectional"))
    )
    (net (code "70") (name "unconnected-(J1-PadD7)") (class "Default")
      (node (ref "J1") (pin "D7") (pinfunction "D7_D7") (pintype "bidirectional"))
    )
    (net (code "71") (name "unconnected-(J1-PadD12)") (class "Default")
      (node (ref "J1") (pin "D12") (pinfunction "D12_D12") (pintype "bidirectional"))
    )
    (net (code "72") (name "unconnected-(J1-PadD13)") (class "Default")
      (node (ref "J1") (pin "D13") (pinfunction "D13_D13") (pintype "bidirectional"))
    )
    (net (code "73") (name "unconnected-(J1-PadRES)") (class "Default")
      (node (ref "J1") (pin "RES") (pinfunction "RES_RES") (pintype "bidirectional"))
    )
    (net (code "74") (name "unconnected-(J1-PadRX)") (class "Default")
      (node (ref "J1") (pin "RX") (pinfunction "RX_RX") (pintype "bidirectional"))
    )
    (net (code "75") (name "unconnected-(J1-PadTX)") (class "Default")
      (node (ref "J1") (pin "TX") (pinfunction "TX_TX") (pintype "bidirectional"))
    )
  )
)
